# SZG-TEMPLATE-STD.net
KiCad netlist of a schematic drawn in Altium Designer
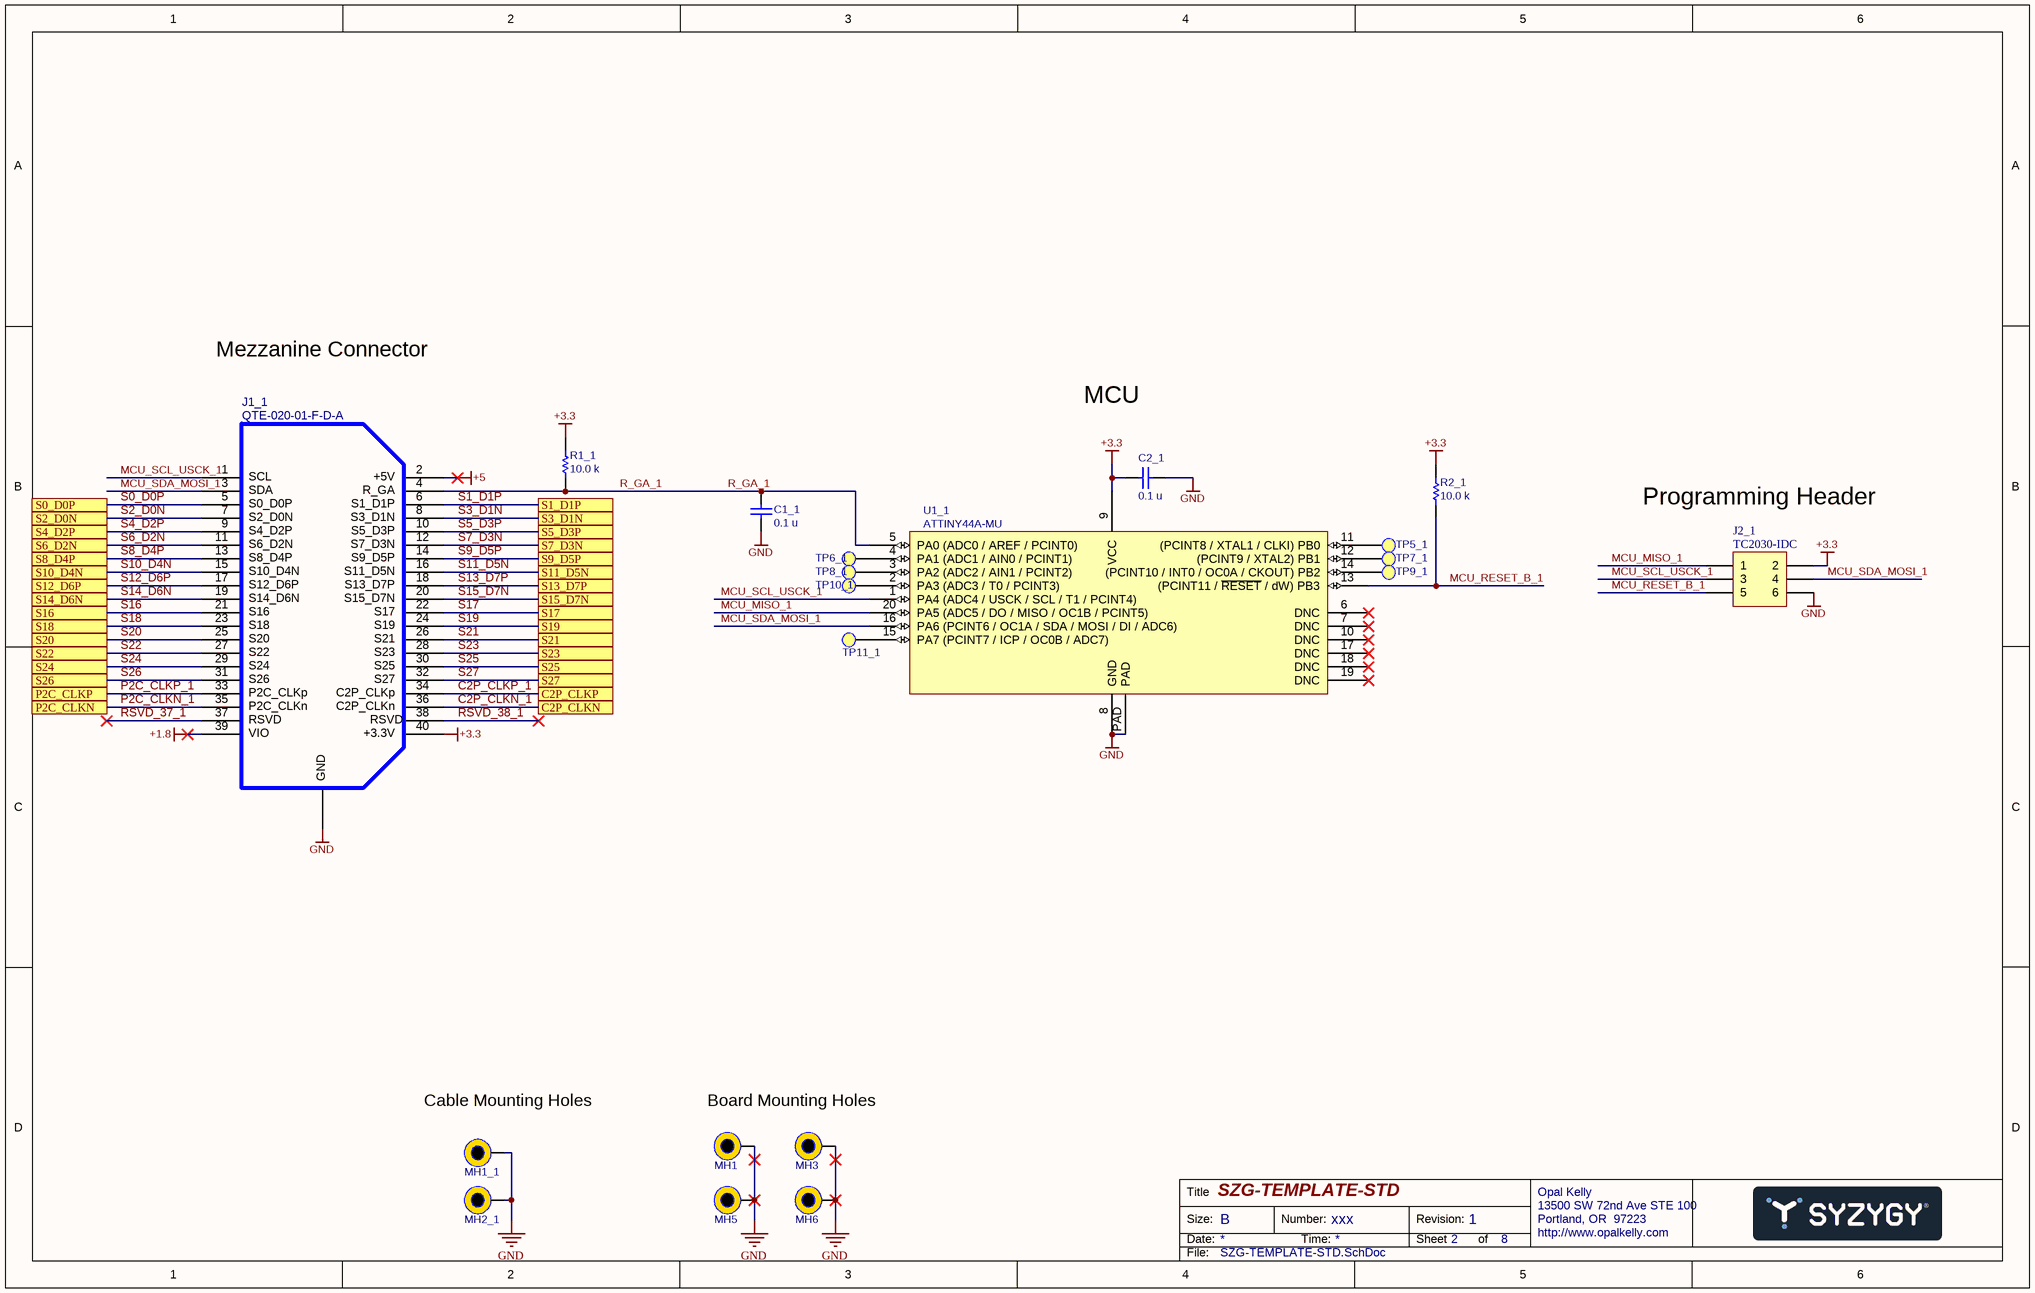
[diagram p0: SZG-TEMPLATE-STD.SchDoc]

(export (version "E")
  (design (tool "Eeschema 10.0.6"))
  (components
    (comp (ref "C1_1")
      (value "0.1 u")
      (footprint "CAPC1005X06N")
      (description "Ceramic capacitor")
      (fields (field (name "MANUFACTURER") "Kemet") (field (name "PARTNUMBER") "000070"))
      (libsource (lib "Aligni") (part "Capacitor"))
    )
    (comp (ref "C2_1")
      (value "0.1 u")
      (footprint "CAPC1005X06N")
      (description "Ceramic capacitor")
      (fields (field (name "MANUFACTURER") "Kemet") (field (name "PARTNUMBER") "000070"))
      (libsource (lib "Aligni") (part "Capacitor"))
    )
    (comp (ref "J1_1")
      (value "QTE-020-01-F-D-A")
      (footprint "QTE-020-01-X-D-A-L")
      (fields (field (name "PARTNUMBER") "000973") (field (name "MANUFACTURER") "Samtec"))
      (libsource (lib "Aligni") (part "QTE_QSE-020"))
    )
    (comp (ref "J2_1")
      (value "~")
      (footprint "TC2030-DUAL")
      (description "Tag-Connect 6-pin Plug-of-Nails spring-pin cable footprint")
      (fields
        (field (name "ALIGNIPARTNUMBER") "002062")
        (field (name "MANUFACTURER") "Tag-Connect")
        (field (name "MANUFACTURER_PN") "TC2030-IDC")
      )
      (libsource (lib "Aligni") (part "Header 3X2"))
    )
    (comp (ref "MH1")
      (value "MTG")
      (footprint "MTG-3.2/6.5-PTH")
      (description "Mounting hole")
      (libsource (lib "NoBOM") (part "MTG"))
    )
    (comp (ref "MH1_1")
      (value "MTG")
      (footprint "MTG-3.2/6.5-PTH")
      (description "Mounting hole")
      (libsource (lib "NoBOM") (part "MTG"))
    )
    (comp (ref "MH2_1")
      (value "MTG")
      (footprint "MTG-3.2/6.5-PTH")
      (description "Mounting hole")
      (libsource (lib "NoBOM") (part "MTG"))
    )
    (comp (ref "MH3")
      (value "MTG")
      (footprint "MTG-3.2/6.5-PTH")
      (description "Mounting hole")
      (libsource (lib "NoBOM") (part "MTG"))
    )
    (comp (ref "MH5")
      (value "MTG")
      (footprint "MTG-3.2/6.5-PTH")
      (description "Mounting hole")
      (libsource (lib "NoBOM") (part "MTG"))
    )
    (comp (ref "MH6")
      (value "MTG")
      (footprint "MTG-3.2/6.5-PTH")
      (description "Mounting hole")
      (libsource (lib "NoBOM") (part "MTG"))
    )
    (comp (ref "R1_1")
      (value "10.0 k")
      (footprint "RESC1005X06N")
      (description "Thick-film resistor")
      (fields (field (name "MANUFACTURER") "Vishay") (field (name "PARTNUMBER") "001521"))
      (libsource (lib "Aligni") (part "Resistor"))
    )
    (comp (ref "R2_1")
      (value "10.0 k")
      (footprint "RESC1005X06N")
      (description "Thick-film resistor")
      (fields (field (name "MANUFACTURER") "Vishay") (field (name "PARTNUMBER") "001521"))
      (libsource (lib "Aligni") (part "Resistor"))
    )
    (comp (ref "TP5_1")
      (value "TESTPOINT-SMD20")
      (footprint "TP-SMD20")
      (description "Test point, surface-mount, 20mil")
      (libsource (lib "NoBOM") (part "TESTPOINT-SMD20"))
    )
    (comp (ref "TP6_1")
      (value "TESTPOINT-SMD20")
      (footprint "TP-SMD20")
      (description "Test point, surface-mount, 20mil")
      (libsource (lib "NoBOM") (part "TESTPOINT-SMD20"))
    )
    (comp (ref "TP7_1")
      (value "TESTPOINT-SMD20")
      (footprint "TP-SMD20")
      (description "Test point, surface-mount, 20mil")
      (libsource (lib "NoBOM") (part "TESTPOINT-SMD20"))
    )
    (comp (ref "TP8_1")
      (value "TESTPOINT-SMD20")
      (footprint "TP-SMD20")
      (description "Test point, surface-mount, 20mil")
      (libsource (lib "NoBOM") (part "TESTPOINT-SMD20"))
    )
    (comp (ref "TP9_1")
      (value "TESTPOINT-SMD20")
      (footprint "TP-SMD20")
      (description "Test point, surface-mount, 20mil")
      (libsource (lib "NoBOM") (part "TESTPOINT-SMD20"))
    )
    (comp (ref "TP10_1")
      (value "TESTPOINT-SMD20")
      (footprint "TP-SMD20")
      (description "Test point, surface-mount, 20mil")
      (libsource (lib "NoBOM") (part "TESTPOINT-SMD20"))
    )
    (comp (ref "TP11_1")
      (value "TESTPOINT-SMD20")
      (footprint "TP-SMD20")
      (description "Test point, surface-mount, 20mil")
      (libsource (lib "NoBOM") (part "TESTPOINT-SMD20"))
    )
    (comp (ref "U1_1")
      (value "ATTINY44A-MU")
      (footprint "QFN-EP-20")
      (description "8-bit MCU, 4 KB flash, 256 bytes EEPROM")
      (fields (field (name "MANUFACTURER") "Microchip") (field (name "PARTNUMBER") "001552"))
      (libsource (lib "Aligni") (part "ATTINYx4A-MU"))
    )
  )
  (nets
    (net (code "1") (name "+1.8") (class "Default")
      (node (ref "J1_1") (pin "39") (pinfunction "39_39") (pintype "passive"))
    )
    (net (code "2") (name "+3.3") (class "Default")
      (node (ref "C2_1") (pin "2") (pinfunction "2_2") (pintype "passive"))
      (node (ref "J1_1") (pin "40") (pinfunction "40_40") (pintype "passive"))
      (node (ref "J2_1") (pin "2") (pinfunction "2_2") (pintype "passive"))
      (node (ref "R1_1") (pin "2") (pinfunction "2_2") (pintype "passive"))
      (node (ref "R2_1") (pin "2") (pinfunction "2_2") (pintype "passive"))
      (node (ref "U1_1") (pin "9") (pinfunction "VCC_9") (pintype "power_in"))
    )
    (net (code "3") (name "+5") (class "Default")
      (node (ref "J1_1") (pin "2") (pinfunction "2_2") (pintype "passive"))
    )
    (net (code "4") (name "/C2P_CLKN_1") (class "Default")
      (node (ref "J1_1") (pin "36") (pinfunction "36_36") (pintype "passive"))
    )
    (net (code "5") (name "/C2P_CLKP_1") (class "Default")
      (node (ref "J1_1") (pin "34") (pinfunction "34_34") (pintype "passive"))
    )
    (net (code "6") (name "/MCU_MISO_1") (class "Default")
      (node (ref "J2_1") (pin "1") (pinfunction "1_1") (pintype "passive"))
      (node (ref "U1_1") (pin "20") (pinfunction "PA5_(ADC5_/_DO_/_MISO_/_OC1B_/_PCINT5)_20") (pintype "bidirectional"))
    )
    (net (code "7") (name "/MCU_RESET_B_1") (class "Default")
      (node (ref "J2_1") (pin "5") (pinfunction "5_5") (pintype "passive"))
      (node (ref "R2_1") (pin "1") (pinfunction "1_1") (pintype "passive"))
      (node (ref "U1_1") (pin "13") (pinfunction "(PCINT11_/_~{RESET}_/_dW)_PB3_13") (pintype "bidirectional"))
    )
    (net (code "8") (name "/MCU_SCL_USCK_1") (class "Default")
      (node (ref "J1_1") (pin "1") (pinfunction "1_1") (pintype "passive"))
      (node (ref "J2_1") (pin "3") (pinfunction "3_3") (pintype "passive"))
      (node (ref "U1_1") (pin "1") (pinfunction "PA4_(ADC4_/_USCK_/_SCL_/_T1_/_PCINT4)_1") (pintype "bidirectional"))
    )
    (net (code "9") (name "/MCU_SDA_MOSI_1") (class "Default")
      (node (ref "J1_1") (pin "3") (pinfunction "3_3") (pintype "passive"))
      (node (ref "J2_1") (pin "4") (pinfunction "4_4") (pintype "passive"))
      (node (ref "U1_1") (pin "16") (pinfunction "PA6_(PCINT6_/_OC1A_/_SDA_/_MOSI_/_DI_/_ADC6)_16") (pintype "bidirectional"))
    )
    (net (code "10") (name "/P2C_CLKN_1") (class "Default")
      (node (ref "J1_1") (pin "35") (pinfunction "35_35") (pintype "passive"))
    )
    (net (code "11") (name "/P2C_CLKP_1") (class "Default")
      (node (ref "J1_1") (pin "33") (pinfunction "33_33") (pintype "passive"))
    )
    (net (code "12") (name "/RSVD_37_1") (class "Default")
      (node (ref "J1_1") (pin "37") (pinfunction "37_37") (pintype "passive+no_connect"))
    )
    (net (code "13") (name "/RSVD_38_1") (class "Default")
      (node (ref "J1_1") (pin "38") (pinfunction "38_38") (pintype "passive+no_connect"))
    )
    (net (code "14") (name "/R_GA_1") (class "Default")
      (node (ref "C1_1") (pin "2") (pinfunction "2_2") (pintype "passive"))
      (node (ref "J1_1") (pin "4") (pinfunction "4_4") (pintype "passive"))
      (node (ref "R1_1") (pin "1") (pinfunction "1_1") (pintype "passive"))
      (node (ref "U1_1") (pin "5") (pinfunction "PA0_(ADC0_/_AREF_/_PCINT0)_5") (pintype "bidirectional"))
    )
    (net (code "15") (name "/S0_D0P") (class "Default")
      (node (ref "J1_1") (pin "5") (pinfunction "5_5") (pintype "passive"))
    )
    (net (code "16") (name "/S1_D1P") (class "Default")
      (node (ref "J1_1") (pin "6") (pinfunction "6_6") (pintype "passive"))
    )
    (net (code "17") (name "/S2_D0N") (class "Default")
      (node (ref "J1_1") (pin "7") (pinfunction "7_7") (pintype "passive"))
    )
    (net (code "18") (name "/S3_D1N") (class "Default")
      (node (ref "J1_1") (pin "8") (pinfunction "8_8") (pintype "passive"))
    )
    (net (code "19") (name "/S4_D2P") (class "Default")
      (node (ref "J1_1") (pin "9") (pinfunction "9_9") (pintype "passive"))
    )
    (net (code "20") (name "/S5_D3P") (class "Default")
      (node (ref "J1_1") (pin "10") (pinfunction "10_10") (pintype "passive"))
    )
    (net (code "21") (name "/S6_D2N") (class "Default")
      (node (ref "J1_1") (pin "11") (pinfunction "11_11") (pintype "passive"))
    )
    (net (code "22") (name "/S7_D3N") (class "Default")
      (node (ref "J1_1") (pin "12") (pinfunction "12_12") (pintype "passive"))
    )
    (net (code "23") (name "/S8_D4P") (class "Default")
      (node (ref "J1_1") (pin "13") (pinfunction "13_13") (pintype "passive"))
    )
    (net (code "24") (name "/S9_D5P") (class "Default")
      (node (ref "J1_1") (pin "14") (pinfunction "14_14") (pintype "passive"))
    )
    (net (code "25") (name "/S10_D4N") (class "Default")
      (node (ref "J1_1") (pin "15") (pinfunction "15_15") (pintype "passive"))
    )
    (net (code "26") (name "/S11_D5N") (class "Default")
      (node (ref "J1_1") (pin "16") (pinfunction "16_16") (pintype "passive"))
    )
    (net (code "27") (name "/S12_D6P") (class "Default")
      (node (ref "J1_1") (pin "17") (pinfunction "17_17") (pintype "passive"))
    )
    (net (code "28") (name "/S13_D7P") (class "Default")
      (node (ref "J1_1") (pin "18") (pinfunction "18_18") (pintype "passive"))
    )
    (net (code "29") (name "/S14_D6N") (class "Default")
      (node (ref "J1_1") (pin "19") (pinfunction "19_19") (pintype "passive"))
    )
    (net (code "30") (name "/S15_D7N") (class "Default")
      (node (ref "J1_1") (pin "20") (pinfunction "20_20") (pintype "passive"))
    )
    (net (code "31") (name "/S16") (class "Default")
      (node (ref "J1_1") (pin "21") (pinfunction "21_21") (pintype "passive"))
    )
    (net (code "32") (name "/S17") (class "Default")
      (node (ref "J1_1") (pin "22") (pinfunction "22_22") (pintype "passive"))
    )
    (net (code "33") (name "/S18") (class "Default")
      (node (ref "J1_1") (pin "23") (pinfunction "23_23") (pintype "passive"))
    )
    (net (code "34") (name "/S19") (class "Default")
      (node (ref "J1_1") (pin "24") (pinfunction "24_24") (pintype "passive"))
    )
    (net (code "35") (name "/S20") (class "Default")
      (node (ref "J1_1") (pin "25") (pinfunction "25_25") (pintype "passive"))
    )
    (net (code "36") (name "/S21") (class "Default")
      (node (ref "J1_1") (pin "26") (pinfunction "26_26") (pintype "passive"))
    )
    (net (code "37") (name "/S22") (class "Default")
      (node (ref "J1_1") (pin "27") (pinfunction "27_27") (pintype "passive"))
    )
    (net (code "38") (name "/S23") (class "Default")
      (node (ref "J1_1") (pin "28") (pinfunction "28_28") (pintype "passive"))
    )
    (net (code "39") (name "/S24") (class "Default")
      (node (ref "J1_1") (pin "29") (pinfunction "29_29") (pintype "passive"))
    )
    (net (code "40") (name "/S25") (class "Default")
      (node (ref "J1_1") (pin "30") (pinfunction "30_30") (pintype "passive"))
    )
    (net (code "41") (name "/S26") (class "Default")
      (node (ref "J1_1") (pin "31") (pinfunction "31_31") (pintype "passive"))
    )
    (net (code "42") (name "/S27") (class "Default")
      (node (ref "J1_1") (pin "32") (pinfunction "32_32") (pintype "passive"))
    )
    (net (code "43") (name "GND") (class "Default")
      (node (ref "C1_1") (pin "1") (pinfunction "1_1") (pintype "passive"))
      (node (ref "C2_1") (pin "1") (pinfunction "1_1") (pintype "passive"))
      (node (ref "J1_1") (pin "0") (pinfunction "0_0") (pintype "passive"))
      (node (ref "J2_1") (pin "6") (pinfunction "6_6") (pintype "passive"))
      (node (ref "MH1") (pin "1") (pinfunction "1_1") (pintype "passive"))
      (node (ref "MH1_1") (pin "1") (pinfunction "1_1") (pintype "passive"))
      (node (ref "MH2_1") (pin "1") (pinfunction "1_1") (pintype "passive"))
      (node (ref "MH3") (pin "1") (pinfunction "1_1") (pintype "passive"))
      (node (ref "MH5") (pin "1") (pinfunction "1_1") (pintype "passive"))
      (node (ref "MH6") (pin "1") (pinfunction "1_1") (pintype "passive"))
      (node (ref "U1_1") (pin "8") (pinfunction "GND_8") (pintype "power_in"))
      (node (ref "U1_1") (pin "PAD") (pinfunction "PAD_PAD") (pintype "power_in"))
    )
    (net (code "44") (name "Net-(TP5_1-PIN)") (class "Default")
      (node (ref "TP5_1") (pin "1") (pinfunction "PIN_1") (pintype "passive"))
      (node (ref "U1_1") (pin "11") (pinfunction "(PCINT8_/_XTAL1_/_CLKI)_PB0_11") (pintype "bidirectional"))
    )
    (net (code "45") (name "Net-(TP6_1-PIN)") (class "Default")
      (node (ref "TP6_1") (pin "1") (pinfunction "PIN_1") (pintype "passive"))
      (node (ref "U1_1") (pin "4") (pinfunction "PA1_(ADC1_/_AIN0_/_PCINT1)_4") (pintype "bidirectional"))
    )
    (net (code "46") (name "Net-(TP7_1-PIN)") (class "Default")
      (node (ref "TP7_1") (pin "1") (pinfunction "PIN_1") (pintype "passive"))
      (node (ref "U1_1") (pin "12") (pinfunction "(PCINT9_/_XTAL2)_PB1_12") (pintype "bidirectional"))
    )
    (net (code "47") (name "Net-(TP8_1-PIN)") (class "Default")
      (node (ref "TP8_1") (pin "1") (pinfunction "PIN_1") (pintype "passive"))
      (node (ref "U1_1") (pin "3") (pinfunction "PA2_(ADC2_/_AIN1_/_PCINT2)_3") (pintype "bidirectional"))
    )
    (net (code "48") (name "Net-(TP9_1-PIN)") (class "Default")
      (node (ref "TP9_1") (pin "1") (pinfunction "PIN_1") (pintype "passive"))
      (node (ref "U1_1") (pin "14") (pinfunction "(PCINT10_/_INT0_/_OC0A_/_CKOUT)_PB2_14") (pintype "bidirectional"))
    )
    (net (code "49") (name "Net-(TP10_1-PIN)") (class "Default")
      (node (ref "TP10_1") (pin "1") (pinfunction "PIN_1") (pintype "passive"))
      (node (ref "U1_1") (pin "2") (pinfunction "PA3_(ADC3_/_T0_/_PCINT3)_2") (pintype "bidirectional"))
    )
    (net (code "50") (name "Net-(TP11_1-PIN)") (class "Default")
      (node (ref "TP11_1") (pin "1") (pinfunction "PIN_1") (pintype "passive"))
      (node (ref "U1_1") (pin "15") (pinfunction "PA7_(PCINT7_/_ICP_/_OC0B_/_ADC7)_15") (pintype "bidirectional"))
    )
    (net (code "51") (name "unconnected-(U1_1-DNC-Pad6)") (class "Default")
      (node (ref "U1_1") (pin "6") (pinfunction "DNC_6") (pintype "passive+no_connect"))
    )
    (net (code "52") (name "unconnected-(U1_1-DNC-Pad7)") (class "Default")
      (node (ref "U1_1") (pin "7") (pinfunction "DNC_7") (pintype "passive+no_connect"))
    )
    (net (code "53") (name "unconnected-(U1_1-DNC-Pad10)") (class "Default")
      (node (ref "U1_1") (pin "10") (pinfunction "DNC_10") (pintype "passive+no_connect"))
    )
    (net (code "54") (name "unconnected-(U1_1-DNC-Pad17)") (class "Default")
      (node (ref "U1_1") (pin "17") (pinfunction "DNC_17") (pintype "passive+no_connect"))
    )
    (net (code "55") (name "unconnected-(U1_1-DNC-Pad18)") (class "Default")
      (node (ref "U1_1") (pin "18") (pinfunction "DNC_18") (pintype "passive+no_connect"))
    )
    (net (code "56") (name "unconnected-(U1_1-DNC-Pad19)") (class "Default")
      (node (ref "U1_1") (pin "19") (pinfunction "DNC_19") (pintype "passive+no_connect"))
    )
  )
)
